# WiFiGeiger.net
KiCad netlist of a schematic drawn in EAGLE
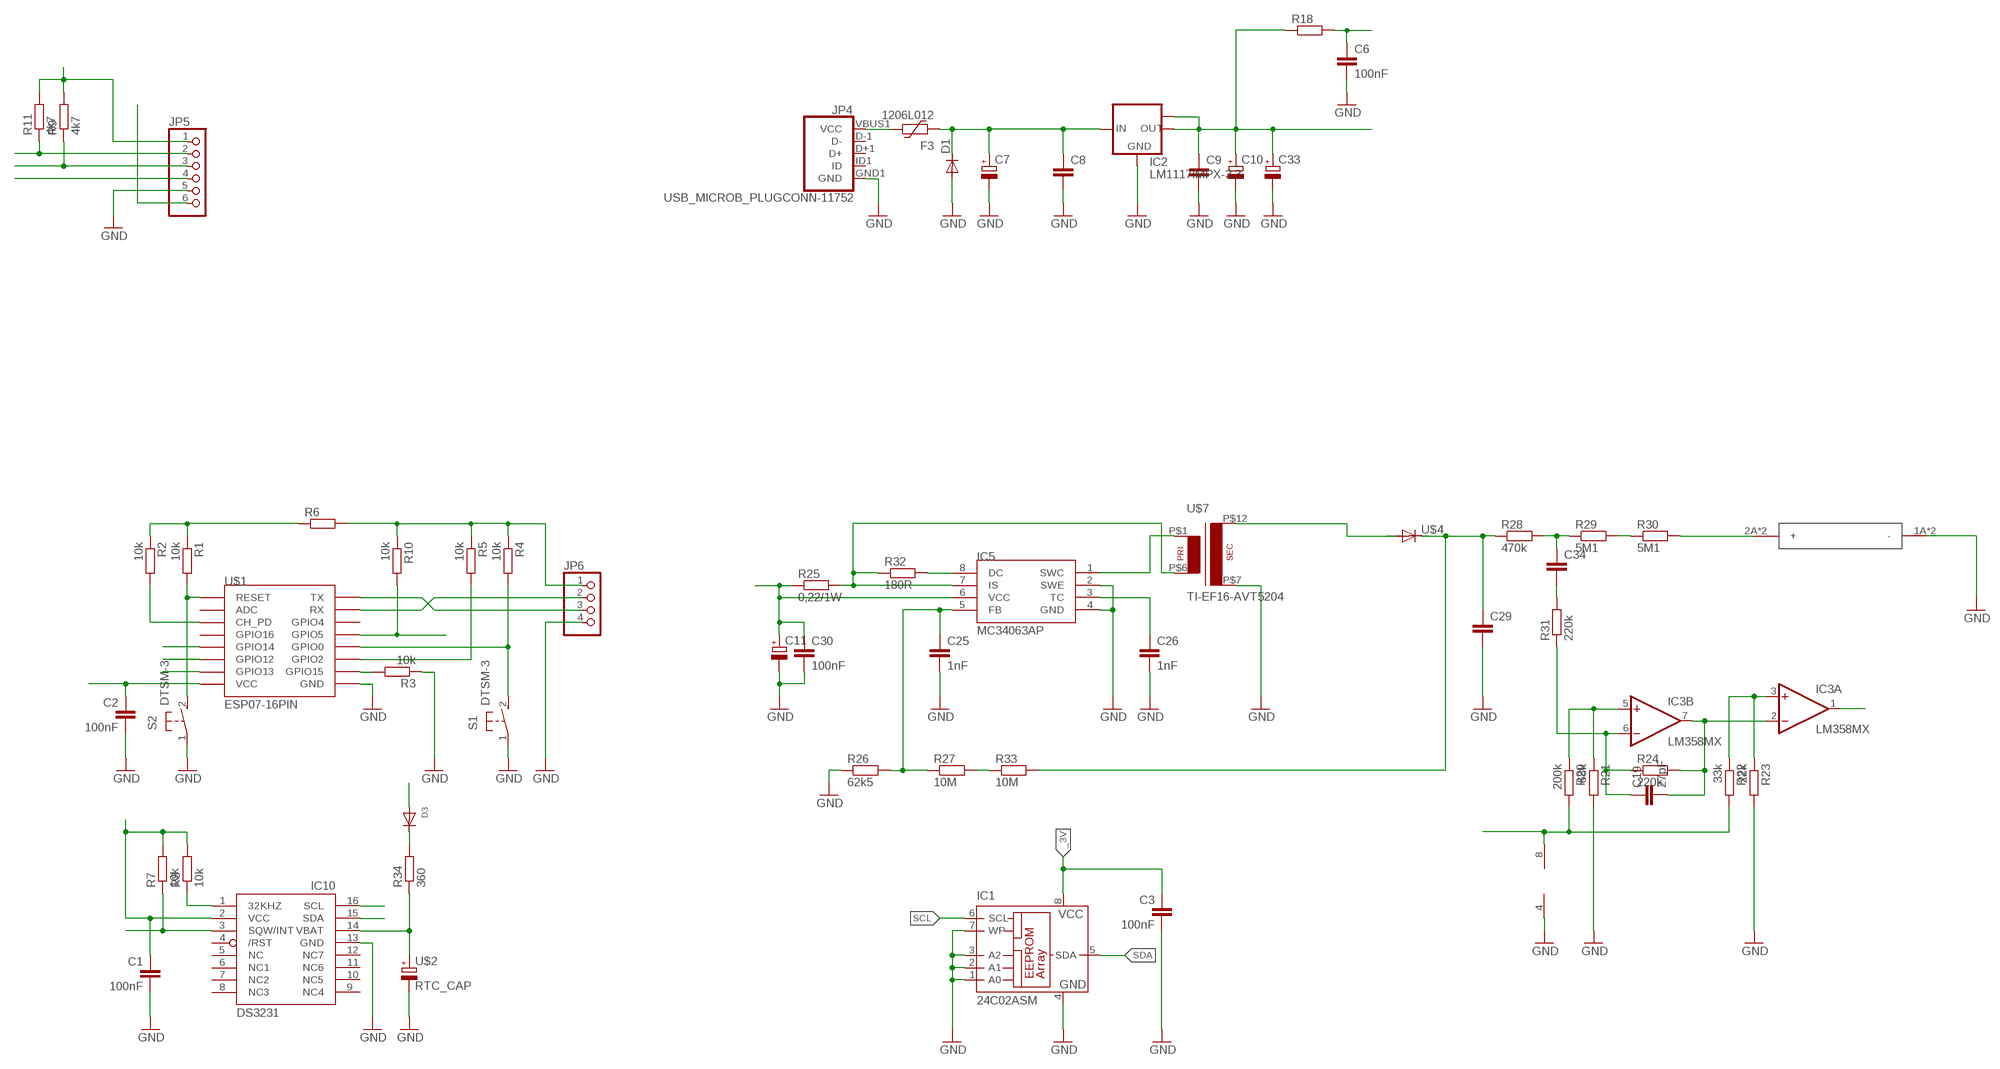
[diagram p0: schematic, sheet 1]

(export (version "E")
  (design (tool "Eeschema 10.0.6"))
  (components
    (comp (ref "C1")
      (value "100nF")
      (footprint "eagle-import:C0603")
      (libsource (lib "eagle-import") (part "C-EUC0603"))
    )
    (comp (ref "C2")
      (value "100nF")
      (footprint "eagle-import:C0603")
      (libsource (lib "eagle-import") (part "C-EUC0603"))
    )
    (comp (ref "C3")
      (value "100nF")
      (footprint "eagle-import:C0603")
      (libsource (lib "eagle-import") (part "C-EUC0603"))
    )
    (comp (ref "C6")
      (value "100nF")
      (footprint "eagle-import:C0603")
      (libsource (lib "eagle-import") (part "C-EUC0603"))
    )
    (comp (ref "C7")
      (value "CPOL-EUSMCC")
      (footprint "eagle-import:SMC_C")
      (libsource (lib "eagle-import") (part "CPOL-EUSMCC"))
    )
    (comp (ref "C8")
      (value "C-EUC1206")
      (footprint "eagle-import:C1206")
      (libsource (lib "eagle-import") (part "C-EUC1206"))
    )
    (comp (ref "C9")
      (value "C-EUC1206")
      (footprint "eagle-import:C1206")
      (libsource (lib "eagle-import") (part "C-EUC1206"))
    )
    (comp (ref "C10")
      (value "CPOL-EUSMCC")
      (footprint "eagle-import:SMC_C")
      (libsource (lib "eagle-import") (part "CPOL-EUSMCC"))
    )
    (comp (ref "C11")
      (value "CPOL-EUSMCE")
      (footprint "eagle-import:SMC_E")
      (libsource (lib "eagle-import") (part "CPOL-EUSMCE"))
    )
    (comp (ref "C19")
      (value "27pF")
      (footprint "eagle-import:C0603")
      (libsource (lib "eagle-import") (part "C-EUC0603"))
    )
    (comp (ref "C25")
      (value "1nF")
      (footprint "eagle-import:C0603")
      (libsource (lib "eagle-import") (part "C-EUC0603"))
    )
    (comp (ref "C26")
      (value "1nF")
      (footprint "eagle-import:C0603")
      (libsource (lib "eagle-import") (part "C-EUC0603"))
    )
    (comp (ref "C29")
      (value "C-EU225-113X268")
      (footprint "eagle-import:C225-113X268")
      (libsource (lib "eagle-import") (part "C-EU225-113X268"))
    )
    (comp (ref "C30")
      (value "100nF")
      (footprint "eagle-import:C0603")
      (libsource (lib "eagle-import") (part "C-EUC0603"))
    )
    (comp (ref "C33")
      (value "CPOL-EUSMCB")
      (footprint "eagle-import:SMC_B")
      (libsource (lib "eagle-import") (part "CPOL-EUSMCB"))
    )
    (comp (ref "C34")
      (value "C-EU050-024X044")
      (footprint "eagle-import:C050-024X044")
      (libsource (lib "eagle-import") (part "C-EU050-024X044"))
    )
    (comp (ref "D1")
      (value "DIODE-SMB")
      (footprint "eagle-import:SMB")
      (libsource (lib "eagle-import") (part "DIODE-SMB"))
    )
    (comp (ref "D3")
      (value "DIODESMA")
      (footprint "eagle-import:SMADIODE")
      (libsource (lib "eagle-import") (part "DIODESMA"))
    )
    (comp (ref "F3")
      (value "1206L012")
      (footprint "eagle-import:1206L")
      (fields (field (name "MF") "Littelfuse"))
      (libsource (lib "eagle-import") (part "?1206L012"))
    )
    (comp (ref "IC1")
      (value "24C02ASM")
      (footprint "eagle-import:SO-08M")
      (fields (field (name "MF") "MICROCHIP") (field (name "MPN") "24C02C/SN"))
      (libsource (lib "eagle-import") (part "24SMC02A"))
    )
    (comp (ref "IC2")
      (value "LM1117IMPX-3.3")
      (footprint "eagle-import:SOT223")
      (libsource (lib "eagle-import") (part "LM1117IMPX-3.3"))
    )
    (comp (ref "IC3")
      (value "LM358MX")
      (footprint "eagle-import:SO08")
      (libsource (lib "eagle-import") (part "LM358MX"))
    )
    (comp (ref "IC5")
      (value "MC34063AP")
      (footprint "eagle-import:DIL08")
      (libsource (lib "eagle-import") (part "MC34063AP"))
    )
    (comp (ref "IC10")
      (value "DS3231/SO")
      (footprint "eagle-import:SO16W")
      (libsource (lib "eagle-import") (part "DS3231/SO"))
    )
    (comp (ref "JP4")
      (value "USB_MICROB_PLUGCONN-11752")
      (footprint "eagle-import:USB-B-MICRO-SMD_V03")
      (libsource (lib "eagle-import") (part "USB_MICROB_PLUGCONN-11752"))
    )
    (comp (ref "JP5")
      (value "PINHD-1X6")
      (footprint "eagle-import:1X06")
      (libsource (lib "eagle-import") (part "PINHD-1X6"))
    )
    (comp (ref "JP6")
      (value "PINHD-1X4")
      (footprint "eagle-import:1X04")
      (libsource (lib "eagle-import") (part "PINHD-1X4"))
    )
    (comp (ref "R1")
      (value "10k")
      (footprint "eagle-import:R0603")
      (libsource (lib "eagle-import") (part "R-EU_R0603"))
    )
    (comp (ref "R2")
      (value "10k")
      (footprint "eagle-import:R0603")
      (libsource (lib "eagle-import") (part "R-EU_R0603"))
    )
    (comp (ref "R3")
      (value "10k")
      (footprint "eagle-import:R0603")
      (libsource (lib "eagle-import") (part "R-EU_R0603"))
    )
    (comp (ref "R4")
      (value "10k")
      (footprint "eagle-import:R0603")
      (libsource (lib "eagle-import") (part "R-EU_R0603"))
    )
    (comp (ref "R5")
      (value "10k")
      (footprint "eagle-import:R0603")
      (libsource (lib "eagle-import") (part "R-EU_R0603"))
    )
    (comp (ref "R6")
      (value "R-EU_R2010")
      (footprint "eagle-import:R2010")
      (libsource (lib "eagle-import") (part "R-EU_R2010"))
    )
    (comp (ref "R7")
      (value "10k")
      (footprint "eagle-import:R0603")
      (libsource (lib "eagle-import") (part "R-EU_R0603"))
    )
    (comp (ref "R8")
      (value "10k")
      (footprint "eagle-import:R0603")
      (libsource (lib "eagle-import") (part "R-EU_R0603"))
    )
    (comp (ref "R9")
      (value "4k7")
      (footprint "eagle-import:R0603")
      (libsource (lib "eagle-import") (part "R-EU_R0603"))
    )
    (comp (ref "R10")
      (value "10k")
      (footprint "eagle-import:R0603")
      (libsource (lib "eagle-import") (part "R-EU_R0603"))
    )
    (comp (ref "R11")
      (value "4k7")
      (footprint "eagle-import:R0603")
      (libsource (lib "eagle-import") (part "R-EU_R0603"))
    )
    (comp (ref "R18")
      (value "R-EU_R1206")
      (footprint "eagle-import:R1206")
      (libsource (lib "eagle-import") (part "R-EU_R1206"))
    )
    (comp (ref "R20")
      (value "200k")
      (footprint "eagle-import:R0603")
      (libsource (lib "eagle-import") (part "R-EU_R0603"))
    )
    (comp (ref "R21")
      (value "68k")
      (footprint "eagle-import:R0603")
      (libsource (lib "eagle-import") (part "R-EU_R0603"))
    )
    (comp (ref "R22")
      (value "33k")
      (footprint "eagle-import:R1206")
      (libsource (lib "eagle-import") (part "R-EU_R1206"))
    )
    (comp (ref "R23")
      (value "22k")
      (footprint "eagle-import:R0603")
      (libsource (lib "eagle-import") (part "R-EU_R0603"))
    )
    (comp (ref "R24")
      (value "220k")
      (footprint "eagle-import:R0603")
      (libsource (lib "eagle-import") (part "R-EU_R0603"))
    )
    (comp (ref "R25")
      (value "0,22/1W")
      (footprint "eagle-import:R2010")
      (libsource (lib "eagle-import") (part "R-EU_R2010"))
    )
    (comp (ref "R26")
      (value "62k5")
      (footprint "eagle-import:R1206")
      (libsource (lib "eagle-import") (part "R-EU_R1206"))
    )
    (comp (ref "R27")
      (value "10M")
      (footprint "eagle-import:R2512")
      (libsource (lib "eagle-import") (part "R-EU_R2512"))
    )
    (comp (ref "R28")
      (value "470k")
      (footprint "eagle-import:R2512")
      (libsource (lib "eagle-import") (part "R-EU_R2512"))
    )
    (comp (ref "R29")
      (value "5M1")
      (footprint "eagle-import:R2512")
      (libsource (lib "eagle-import") (part "R-EU_R2512"))
    )
    (comp (ref "R30")
      (value "5M1")
      (footprint "eagle-import:R2512")
      (libsource (lib "eagle-import") (part "R-EU_R2512"))
    )
    (comp (ref "R31")
      (value "220k")
      (footprint "eagle-import:R0805")
      (libsource (lib "eagle-import") (part "R-EU_R0805"))
    )
    (comp (ref "R32")
      (value "180R")
      (footprint "eagle-import:R0805")
      (libsource (lib "eagle-import") (part "R-EU_R0805"))
    )
    (comp (ref "R33")
      (value "10M")
      (footprint "eagle-import:R2512")
      (libsource (lib "eagle-import") (part "R-EU_R2512"))
    )
    (comp (ref "R34")
      (value "360")
      (footprint "eagle-import:R0603")
      (libsource (lib "eagle-import") (part "R-EU_R0603"))
    )
    (comp (ref "S1")
      (value "DTSM-3")
      (footprint "eagle-import:DTSM-3")
      (libsource (lib "eagle-import") (part "DTSM-3"))
    )
    (comp (ref "S2")
      (value "DTSM-3")
      (footprint "eagle-import:DTSM-3")
      (libsource (lib "eagle-import") (part "DTSM-3"))
    )
    (comp (ref "U$1")
      (value "ESP07-16PIN")
      (footprint "eagle-import:ESP07-16PIN")
      (libsource (lib "eagle-import") (part "ESP07-16PIN"))
    )
    (comp (ref "U$2")
      (value "RTC_CAP")
      (footprint "eagle-import:RTC_CAP")
      (libsource (lib "eagle-import") (part "RTC_CAP"))
    )
    (comp (ref "U$4")
      (value "DIODE-MELF-MLL41")
      (footprint "eagle-import:MELF-MLL41")
      (libsource (lib "eagle-import") (part "DIODE-MELF-MLL41"))
    )
    (comp (ref "U$5")
      (value "STS5")
      (footprint "eagle-import:GEIGERTUBE")
      (libsource (lib "eagle-import") (part "STS5"))
    )
    (comp (ref "U$7")
      (value "TI-EF16-AVT5204")
      (footprint "eagle-import:EF16-K-H-12P-12,5")
      (libsource (lib "eagle-import") (part "TI-EF16-AVT5204"))
    )
  )
  (nets
    (net (code "1") (name "/A_3V") (class "Default")
      (node (ref "C6") (pin "1") (pinfunction "1_1") (pintype "passive"))
      (node (ref "IC3") (pin "8") (pinfunction "V+_8") (pintype "power_in"))
      (node (ref "R18") (pin "2") (pinfunction "2_2") (pintype "passive"))
      (node (ref "R20") (pin "2") (pinfunction "2_2") (pintype "passive"))
      (node (ref "R22") (pin "2") (pinfunction "2_2") (pintype "passive"))
    )
    (net (code "2") (name "/CPM") (class "Default")
      (node (ref "IC3") (pin "1") (pinfunction "OUT_1") (pintype "output"))
      (node (ref "R10") (pin "2") (pinfunction "2_2") (pintype "passive"))
      (node (ref "U$1") (pin "GPIO5") (pinfunction "GPIO5_GPIO5") (pintype "bidirectional"))
    )
    (net (code "3") (name "/SQW") (class "Default")
      (node (ref "IC10") (pin "3") (pinfunction "SQW/INT_3") (pintype "output"))
      (node (ref "R7") (pin "1") (pinfunction "1_1") (pintype "passive"))
      (node (ref "U$1") (pin "GPIO14") (pinfunction "GPIO14_GPIO14") (pintype "bidirectional"))
    )
    (net (code "4") (name "/VBUS") (class "Default")
      (node (ref "C11") (pin "+") (pinfunction "+_+") (pintype "passive"))
      (node (ref "C30") (pin "1") (pinfunction "1_1") (pintype "passive"))
      (node (ref "C7") (pin "+") (pinfunction "+_+") (pintype "passive"))
      (node (ref "C8") (pin "1") (pinfunction "1_1") (pintype "passive"))
      (node (ref "D1") (pin "C") (pinfunction "C_C") (pintype "passive"))
      (node (ref "F3") (pin "2") (pinfunction "2_2") (pintype "passive"))
      (node (ref "IC2") (pin "3") (pinfunction "IN_3") (pintype "input"))
      (node (ref "IC5") (pin "6") (pinfunction "VCC_6") (pintype "passive"))
      (node (ref "JP5") (pin "6") (pinfunction "6_6") (pintype "passive"))
      (node (ref "R25") (pin "1") (pinfunction "1_1") (pintype "passive"))
    )
    (net (code "5") (name "GND") (class "Default")
      (node (ref "C1") (pin "2") (pinfunction "2_2") (pintype "passive"))
      (node (ref "C10") (pin "-") (pinfunction "-_-") (pintype "passive"))
      (node (ref "C11") (pin "-") (pinfunction "-_-") (pintype "passive"))
      (node (ref "C2") (pin "2") (pinfunction "2_2") (pintype "passive"))
      (node (ref "C25") (pin "2") (pinfunction "2_2") (pintype "passive"))
      (node (ref "C26") (pin "2") (pinfunction "2_2") (pintype "passive"))
      (node (ref "C29") (pin "2") (pinfunction "2_2") (pintype "passive"))
      (node (ref "C3") (pin "2") (pinfunction "2_2") (pintype "passive"))
      (node (ref "C30") (pin "2") (pinfunction "2_2") (pintype "passive"))
      (node (ref "C33") (pin "-") (pinfunction "-_-") (pintype "passive"))
      (node (ref "C6") (pin "2") (pinfunction "2_2") (pintype "passive"))
      (node (ref "C7") (pin "-") (pinfunction "-_-") (pintype "passive"))
      (node (ref "C8") (pin "2") (pinfunction "2_2") (pintype "passive"))
      (node (ref "C9") (pin "2") (pinfunction "2_2") (pintype "passive"))
      (node (ref "D1") (pin "A") (pinfunction "A_A") (pintype "passive"))
      (node (ref "IC1") (pin "1") (pinfunction "A0_1") (pintype "input"))
      (node (ref "IC1") (pin "2") (pinfunction "A1_2") (pintype "input"))
      (node (ref "IC1") (pin "3") (pinfunction "A2_3") (pintype "input"))
      (node (ref "IC1") (pin "4") (pinfunction "GND_4") (pintype "power_in"))
      (node (ref "IC1") (pin "7") (pinfunction "WP_7") (pintype "input"))
      (node (ref "IC10") (pin "13") (pinfunction "GND_13") (pintype "power_in"))
      (node (ref "IC2") (pin "1") (pinfunction "GND_1") (pintype "input"))
      (node (ref "IC3") (pin "4") (pinfunction "V-_4") (pintype "power_in"))
      (node (ref "IC5") (pin "2") (pinfunction "SWE_2") (pintype "passive"))
      (node (ref "IC5") (pin "4") (pinfunction "GND_4") (pintype "passive"))
      (node (ref "JP4") (pin "GND1") (pinfunction "GND_GND1") (pintype "bidirectional"))
      (node (ref "JP5") (pin "5") (pinfunction "5_5") (pintype "passive"))
      (node (ref "JP6") (pin "4") (pinfunction "4_4") (pintype "passive"))
      (node (ref "R21") (pin "2") (pinfunction "2_2") (pintype "passive"))
      (node (ref "R23") (pin "2") (pinfunction "2_2") (pintype "passive"))
      (node (ref "R26") (pin "1") (pinfunction "1_1") (pintype "passive"))
      (node (ref "R3") (pin "1") (pinfunction "1_1") (pintype "passive"))
      (node (ref "S1") (pin "1") (pinfunction "1_1") (pintype "passive"))
      (node (ref "S2") (pin "1") (pinfunction "1_1") (pintype "passive"))
      (node (ref "U$1") (pin "GND") (pinfunction "GND_GND") (pintype "bidirectional"))
      (node (ref "U$2") (pin "P$2") (pinfunction "-_P$2") (pintype "passive"))
      (node (ref "U$5") (pin "1A") (pinfunction "-_1A") (pintype "bidirectional"))
      (node (ref "U$5") (pin "1B") (pinfunction "-_1B") (pintype "bidirectional"))
      (node (ref "U$7") (pin "P$7") (pinfunction "P7_P$7") (pintype "passive"))
    )
    (net (code "6") (name "Net-(C29-Pad1)") (class "Default")
      (node (ref "C29") (pin "1") (pinfunction "1_1") (pintype "passive"))
      (node (ref "R28") (pin "1") (pinfunction "1_1") (pintype "passive"))
      (node (ref "R33") (pin "2") (pinfunction "2_2") (pintype "passive"))
      (node (ref "U$4") (pin "C") (pinfunction "C_C") (pintype "passive"))
    )
    (net (code "7") (name "Net-(C34-Pad1)") (class "Default")
      (node (ref "C34") (pin "1") (pinfunction "1_1") (pintype "passive"))
      (node (ref "R28") (pin "2") (pinfunction "2_2") (pintype "passive"))
      (node (ref "R29") (pin "1") (pinfunction "1_1") (pintype "passive"))
    )
    (net (code "8") (name "Net-(C34-Pad2)") (class "Default")
      (node (ref "C34") (pin "2") (pinfunction "2_2") (pintype "passive"))
      (node (ref "R31") (pin "2") (pinfunction "2_2") (pintype "passive"))
    )
    (net (code "9") (name "Net-(D3-PadC)") (class "Default")
      (node (ref "D3") (pin "C") (pinfunction "C_C") (pintype "passive"))
      (node (ref "R34") (pin "2") (pinfunction "2_2") (pintype "passive"))
    )
    (net (code "10") (name "Net-(IC3A-+IN)") (class "Default")
      (node (ref "IC3") (pin "3") (pinfunction "+IN_3") (pintype "input"))
      (node (ref "R22") (pin "1") (pinfunction "1_1") (pintype "passive"))
      (node (ref "R23") (pin "1") (pinfunction "1_1") (pintype "passive"))
    )
    (net (code "11") (name "Net-(IC3A--IN)") (class "Default")
      (node (ref "C19") (pin "2") (pinfunction "2_2") (pintype "passive"))
      (node (ref "IC3") (pin "2") (pinfunction "-IN_2") (pintype "input"))
      (node (ref "IC3") (pin "7") (pinfunction "OUT_7") (pintype "output"))
      (node (ref "R24") (pin "2") (pinfunction "2_2") (pintype "passive"))
    )
    (net (code "12") (name "Net-(IC3B-+IN)") (class "Default")
      (node (ref "IC3") (pin "5") (pinfunction "+IN_5") (pintype "input"))
      (node (ref "R20") (pin "1") (pinfunction "1_1") (pintype "passive"))
      (node (ref "R21") (pin "1") (pinfunction "1_1") (pintype "passive"))
    )
    (net (code "13") (name "Net-(IC3B--IN)") (class "Default")
      (node (ref "C19") (pin "1") (pinfunction "1_1") (pintype "passive"))
      (node (ref "IC3") (pin "6") (pinfunction "-IN_6") (pintype "input"))
      (node (ref "R24") (pin "1") (pinfunction "1_1") (pintype "passive"))
      (node (ref "R31") (pin "1") (pinfunction "1_1") (pintype "passive"))
    )
    (net (code "14") (name "Net-(IC5-DC)") (class "Default")
      (node (ref "IC5") (pin "8") (pinfunction "DC_8") (pintype "passive"))
      (node (ref "R32") (pin "2") (pinfunction "2_2") (pintype "passive"))
    )
    (net (code "15") (name "Net-(IC5-FB)") (class "Default")
      (node (ref "C25") (pin "1") (pinfunction "1_1") (pintype "passive"))
      (node (ref "IC5") (pin "5") (pinfunction "FB_5") (pintype "passive"))
      (node (ref "R26") (pin "2") (pinfunction "2_2") (pintype "passive"))
      (node (ref "R27") (pin "1") (pinfunction "1_1") (pintype "passive"))
    )
    (net (code "16") (name "Net-(IC5-IS)") (class "Default")
      (node (ref "IC5") (pin "7") (pinfunction "IS_7") (pintype "passive"))
      (node (ref "R25") (pin "2") (pinfunction "2_2") (pintype "passive"))
      (node (ref "R32") (pin "1") (pinfunction "1_1") (pintype "passive"))
      (node (ref "U$7") (pin "P$6") (pinfunction "P6_P$6") (pintype "passive"))
    )
    (net (code "17") (name "Net-(IC5-SWC)") (class "Default")
      (node (ref "IC5") (pin "1") (pinfunction "SWC_1") (pintype "passive"))
      (node (ref "U$7") (pin "P$1") (pinfunction "P1_P$1") (pintype "passive"))
    )
    (net (code "18") (name "Net-(IC5-TC)") (class "Default")
      (node (ref "C26") (pin "1") (pinfunction "1_1") (pintype "passive"))
      (node (ref "IC5") (pin "3") (pinfunction "TC_3") (pintype "passive"))
    )
    (net (code "19") (name "Net-(IC10-32KHZ)") (class "Default")
      (node (ref "IC10") (pin "1") (pinfunction "32KHZ_1") (pintype "output"))
      (node (ref "R8") (pin "1") (pinfunction "1_1") (pintype "passive"))
    )
    (net (code "20") (name "Net-(IC10-VBAT)") (class "Default")
      (node (ref "IC10") (pin "14") (pinfunction "VBAT_14") (pintype "power_in"))
      (node (ref "R34") (pin "1") (pinfunction "1_1") (pintype "passive"))
      (node (ref "U$2") (pin "P$1") (pinfunction "+_P$1") (pintype "passive"))
    )
    (net (code "21") (name "Net-(JP4-VCC)") (class "Default")
      (node (ref "F3") (pin "1") (pinfunction "1_1") (pintype "passive"))
      (node (ref "JP4") (pin "VBUS1") (pinfunction "VCC_VBUS1") (pintype "bidirectional"))
    )
    (net (code "22") (name "Net-(JP6-Pad1)") (class "Default")
      (node (ref "JP6") (pin "1") (pinfunction "1_1") (pintype "passive"))
      (node (ref "R10") (pin "1") (pinfunction "1_1") (pintype "passive"))
      (node (ref "R4") (pin "1") (pinfunction "1_1") (pintype "passive"))
      (node (ref "R5") (pin "1") (pinfunction "1_1") (pintype "passive"))
      (node (ref "R6") (pin "2") (pinfunction "2_2") (pintype "passive"))
    )
    (net (code "23") (name "Net-(JP6-Pad2)") (class "Default")
      (node (ref "JP6") (pin "2") (pinfunction "2_2") (pintype "passive"))
      (node (ref "U$1") (pin "RX") (pinfunction "RX_RX") (pintype "bidirectional"))
    )
    (net (code "24") (name "Net-(JP6-Pad3)") (class "Default")
      (node (ref "JP6") (pin "3") (pinfunction "3_3") (pintype "passive"))
      (node (ref "U$1") (pin "TX") (pinfunction "TX_TX") (pintype "bidirectional"))
    )
    (net (code "25") (name "Net-(R2-Pad2)") (class "Default")
      (node (ref "R2") (pin "2") (pinfunction "2_2") (pintype "passive"))
      (node (ref "U$1") (pin "CH_PD") (pinfunction "CH_PD_CH_PD") (pintype "bidirectional"))
    )
    (net (code "26") (name "Net-(R3-Pad2)") (class "Default")
      (node (ref "R3") (pin "2") (pinfunction "2_2") (pintype "passive"))
      (node (ref "U$1") (pin "GPIO15") (pinfunction "GPIO15_GPIO15") (pintype "bidirectional"))
    )
    (net (code "27") (name "Net-(R4-Pad2)") (class "Default")
      (node (ref "R4") (pin "2") (pinfunction "2_2") (pintype "passive"))
      (node (ref "S1") (pin "2") (pinfunction "2_2") (pintype "passive"))
      (node (ref "U$1") (pin "GPIO0") (pinfunction "GPIO0_GPIO0") (pintype "bidirectional"))
    )
    (net (code "28") (name "Net-(R5-Pad2)") (class "Default")
      (node (ref "R5") (pin "2") (pinfunction "2_2") (pintype "passive"))
      (node (ref "U$1") (pin "GPIO2") (pinfunction "GPIO2_GPIO2") (pintype "bidirectional"))
    )
    (net (code "29") (name "Net-(R27-Pad2)") (class "Default")
      (node (ref "R27") (pin "2") (pinfunction "2_2") (pintype "passive"))
      (node (ref "R33") (pin "1") (pinfunction "1_1") (pintype "passive"))
    )
    (net (code "30") (name "Net-(R29-Pad2)") (class "Default")
      (node (ref "R29") (pin "2") (pinfunction "2_2") (pintype "passive"))
      (node (ref "R30") (pin "1") (pinfunction "1_1") (pintype "passive"))
    )
    (net (code "31") (name "Net-(R30-Pad2)") (class "Default")
      (node (ref "R30") (pin "2") (pinfunction "2_2") (pintype "passive"))
      (node (ref "U$5") (pin "2A") (pinfunction "+_2A") (pintype "bidirectional"))
      (node (ref "U$5") (pin "2B") (pinfunction "+_2B") (pintype "bidirectional"))
    )
    (net (code "32") (name "Net-(U$1-RESET)") (class "Default")
      (node (ref "R1") (pin "2") (pinfunction "2_2") (pintype "passive"))
      (node (ref "S2") (pin "2") (pinfunction "2_2") (pintype "passive"))
      (node (ref "U$1") (pin "REST") (pinfunction "RESET_REST") (pintype "bidirectional"))
    )
    (net (code "33") (name "Net-(U$7-P12)") (class "Default")
      (node (ref "U$4") (pin "A") (pinfunction "A_A") (pintype "passive"))
      (node (ref "U$7") (pin "P$12") (pinfunction "P12_P$12") (pintype "passive"))
    )
    (net (code "34") (name "SCL") (class "Default")
      (node (ref "IC1") (pin "6") (pinfunction "SCL_6") (pintype "input"))
      (node (ref "IC10") (pin "16") (pinfunction "SCL_16") (pintype "bidirectional"))
      (node (ref "JP5") (pin "3") (pinfunction "3_3") (pintype "passive"))
      (node (ref "R9") (pin "1") (pinfunction "1_1") (pintype "passive"))
      (node (ref "U$1") (pin "GPIO12") (pinfunction "GPIO12_GPIO12") (pintype "bidirectional"))
    )
    (net (code "35") (name "SDA") (class "Default")
      (node (ref "IC1") (pin "5") (pinfunction "SDA_5") (pintype "bidirectional"))
      (node (ref "IC10") (pin "15") (pinfunction "SDA_15") (pintype "bidirectional"))
      (node (ref "JP5") (pin "2") (pinfunction "2_2") (pintype "passive"))
      (node (ref "R11") (pin "1") (pinfunction "1_1") (pintype "passive"))
      (node (ref "U$1") (pin "GPIO13") (pinfunction "GPIO13_GPIO13") (pintype "bidirectional"))
    )
    (net (code "36") (name "_3V") (class "Default")
      (node (ref "C1") (pin "1") (pinfunction "1_1") (pintype "passive"))
      (node (ref "C10") (pin "+") (pinfunction "+_+") (pintype "passive"))
      (node (ref "C2") (pin "1") (pinfunction "1_1") (pintype "passive"))
      (node (ref "C3") (pin "1") (pinfunction "1_1") (pintype "passive"))
      (node (ref "C33") (pin "+") (pinfunction "+_+") (pintype "passive"))
      (node (ref "C9") (pin "1") (pinfunction "1_1") (pintype "passive"))
      (node (ref "D3") (pin "A") (pinfunction "A_A") (pintype "passive"))
      (node (ref "IC1") (pin "8") (pinfunction "VCC_8") (pintype "power_in"))
      (node (ref "IC10") (pin "2") (pinfunction "VCC_2") (pintype "power_in"))
      (node (ref "IC2") (pin "2") (pinfunction "OUT_2") (pintype "passive"))
      (node (ref "IC2") (pin "TAB") (pinfunction "OUT1_TAB") (pintype "passive"))
      (node (ref "JP5") (pin "1") (pinfunction "1_1") (pintype "passive"))
      (node (ref "R1") (pin "1") (pinfunction "1_1") (pintype "passive"))
      (node (ref "R11") (pin "2") (pinfunction "2_2") (pintype "passive"))
      (node (ref "R18") (pin "1") (pinfunction "1_1") (pintype "passive"))
      (node (ref "R2") (pin "1") (pinfunction "1_1") (pintype "passive"))
      (node (ref "R6") (pin "1") (pinfunction "1_1") (pintype "passive"))
      (node (ref "R7") (pin "2") (pinfunction "2_2") (pintype "passive"))
      (node (ref "R8") (pin "2") (pinfunction "2_2") (pintype "passive"))
      (node (ref "R9") (pin "2") (pinfunction "2_2") (pintype "passive"))
      (node (ref "U$1") (pin "VCC") (pinfunction "VCC_VCC") (pintype "bidirectional"))
    )
    (net (code "37") (name "unconnected-(IC10-NC-Pad5)") (class "Default")
      (node (ref "IC10") (pin "5") (pinfunction "NC_5") (pintype "no_connect"))
    )
    (net (code "38") (name "unconnected-(IC10-NC1-Pad6)") (class "Default")
      (node (ref "IC10") (pin "6") (pinfunction "NC1_6") (pintype "no_connect"))
    )
    (net (code "39") (name "unconnected-(IC10-NC2-Pad7)") (class "Default")
      (node (ref "IC10") (pin "7") (pinfunction "NC2_7") (pintype "no_connect"))
    )
    (net (code "40") (name "unconnected-(IC10-NC3-Pad8)") (class "Default")
      (node (ref "IC10") (pin "8") (pinfunction "NC3_8") (pintype "no_connect"))
    )
    (net (code "41") (name "unconnected-(IC10-NC4-Pad9)") (class "Default")
      (node (ref "IC10") (pin "9") (pinfunction "NC4_9") (pintype "no_connect"))
    )
    (net (code "42") (name "unconnected-(IC10-NC5-Pad10)") (class "Default")
      (node (ref "IC10") (pin "10") (pinfunction "NC5_10") (pintype "no_connect"))
    )
    (net (code "43") (name "unconnected-(IC10-NC6-Pad11)") (class "Default")
      (node (ref "IC10") (pin "11") (pinfunction "NC6_11") (pintype "no_connect"))
    )
    (net (code "44") (name "unconnected-(IC10-NC7-Pad12)") (class "Default")
      (node (ref "IC10") (pin "12") (pinfunction "NC7_12") (pintype "no_connect"))
    )
    (net (code "45") (name "unconnected-(IC10-{slash}RST-Pad4)") (class "Default")
      (node (ref "IC10") (pin "4") (pinfunction "/RST_4") (pintype "passive"))
    )
    (net (code "46") (name "unconnected-(JP4-D+-PadD+1)") (class "Default")
      (node (ref "JP4") (pin "D+1") (pinfunction "D+_D+1") (pintype "bidirectional"))
    )
    (net (code "47") (name "unconnected-(JP4-D--PadD-1)") (class "Default")
      (node (ref "JP4") (pin "D-1") (pinfunction "D-_D-1") (pintype "bidirectional"))
    )
    (net (code "48") (name "unconnected-(JP4-ID-PadID1)") (class "Default")
      (node (ref "JP4") (pin "ID1") (pinfunction "ID_ID1") (pintype "bidirectional"))
    )
    (net (code "49") (name "unconnected-(JP5-Pad4)") (class "Default")
      (node (ref "JP5") (pin "4") (pinfunction "4_4") (pintype "passive"))
    )
    (net (code "50") (name "unconnected-(U$1-PadADC)") (class "Default")
      (node (ref "U$1") (pin "ADC") (pinfunction "ADC_ADC") (pintype "bidirectional"))
    )
    (net (code "51") (name "unconnected-(U$1-PadGPIO4)") (class "Default")
      (node (ref "U$1") (pin "GPIO4") (pinfunction "GPIO4_GPIO4") (pintype "bidirectional"))
    )
    (net (code "52") (name "unconnected-(U$1-PadGPIO16)") (class "Default")
      (node (ref "U$1") (pin "GPIO16") (pinfunction "GPIO16_GPIO16") (pintype "bidirectional"))
    )
  )
)
